# W032X.net
KiCad netlist of a schematic drawn in EAGLE
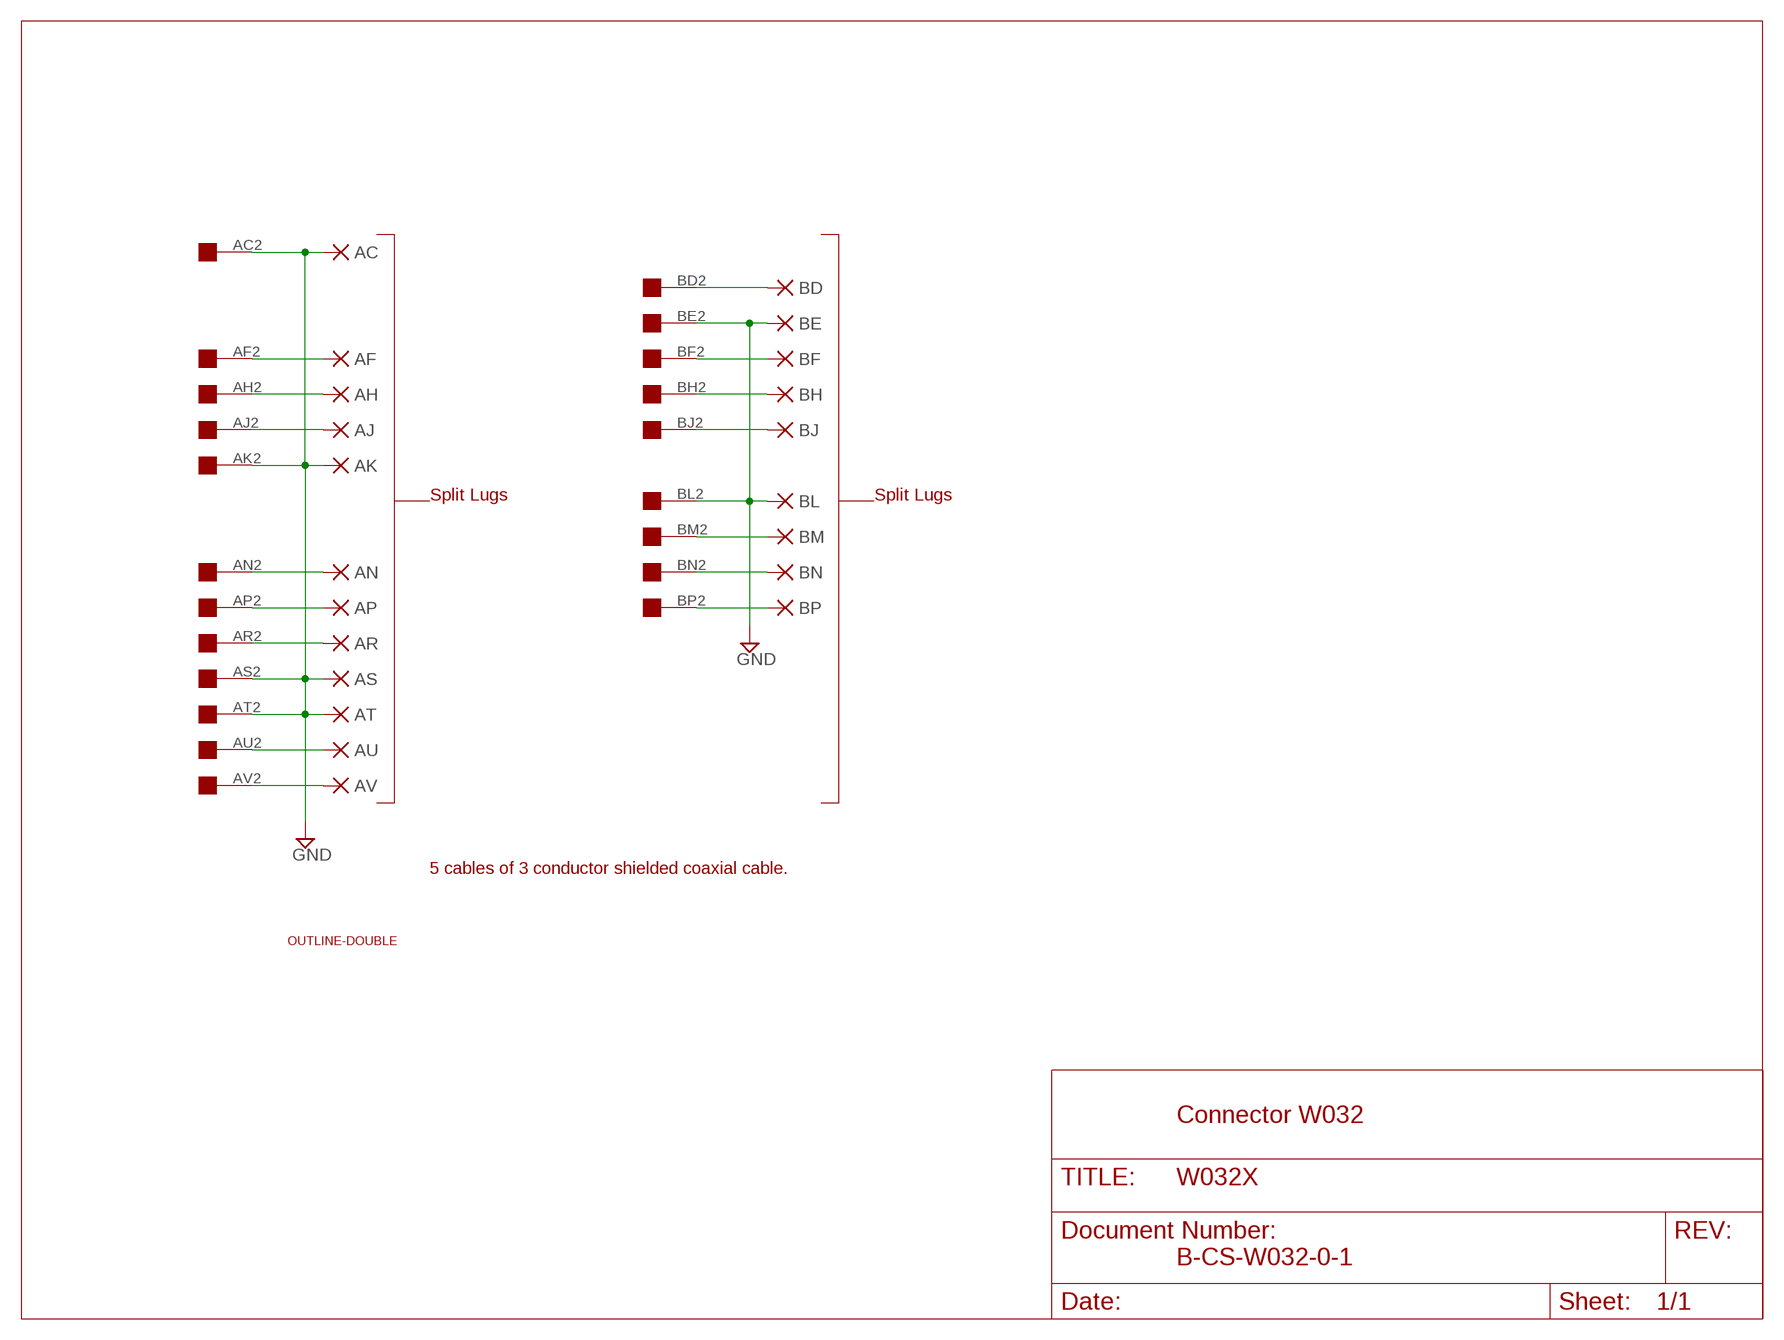
[diagram p0: schematic, sheet 1]

(export (version "E")
  (design (tool "Eeschema 10.0.6"))
  (components
    (comp (ref "AC")
      (value "PAD-0465")
      (footprint "eagle-import:0465")
      (libsource (lib "eagle-import") (part "PAD-0465"))
    )
    (comp (ref "AF")
      (value "PAD-0465")
      (footprint "eagle-import:0465")
      (libsource (lib "eagle-import") (part "PAD-0465"))
    )
    (comp (ref "AH")
      (value "PAD-0465")
      (footprint "eagle-import:0465")
      (libsource (lib "eagle-import") (part "PAD-0465"))
    )
    (comp (ref "AJ")
      (value "PAD-0465")
      (footprint "eagle-import:0465")
      (libsource (lib "eagle-import") (part "PAD-0465"))
    )
    (comp (ref "AK")
      (value "PAD-0465")
      (footprint "eagle-import:0465")
      (libsource (lib "eagle-import") (part "PAD-0465"))
    )
    (comp (ref "AN")
      (value "PAD-0465")
      (footprint "eagle-import:0465")
      (libsource (lib "eagle-import") (part "PAD-0465"))
    )
    (comp (ref "AP")
      (value "PAD-0465")
      (footprint "eagle-import:0465")
      (libsource (lib "eagle-import") (part "PAD-0465"))
    )
    (comp (ref "AR")
      (value "PAD-0465")
      (footprint "eagle-import:0465")
      (libsource (lib "eagle-import") (part "PAD-0465"))
    )
    (comp (ref "AS")
      (value "PAD-0465")
      (footprint "eagle-import:0465")
      (libsource (lib "eagle-import") (part "PAD-0465"))
    )
    (comp (ref "AT")
      (value "PAD-0465")
      (footprint "eagle-import:0465")
      (libsource (lib "eagle-import") (part "PAD-0465"))
    )
    (comp (ref "AU")
      (value "PAD-0465")
      (footprint "eagle-import:0465")
      (libsource (lib "eagle-import") (part "PAD-0465"))
    )
    (comp (ref "AV")
      (value "PAD-0465")
      (footprint "eagle-import:0465")
      (libsource (lib "eagle-import") (part "PAD-0465"))
    )
    (comp (ref "BD")
      (value "PAD-0465")
      (footprint "eagle-import:0465")
      (libsource (lib "eagle-import") (part "PAD-0465"))
    )
    (comp (ref "BE")
      (value "PAD-0465")
      (footprint "eagle-import:0465")
      (libsource (lib "eagle-import") (part "PAD-0465"))
    )
    (comp (ref "BF")
      (value "PAD-0465")
      (footprint "eagle-import:0465")
      (libsource (lib "eagle-import") (part "PAD-0465"))
    )
    (comp (ref "BH")
      (value "PAD-0465")
      (footprint "eagle-import:0465")
      (libsource (lib "eagle-import") (part "PAD-0465"))
    )
    (comp (ref "BJ")
      (value "PAD-0465")
      (footprint "eagle-import:0465")
      (libsource (lib "eagle-import") (part "PAD-0465"))
    )
    (comp (ref "BL")
      (value "PAD-0465")
      (footprint "eagle-import:0465")
      (libsource (lib "eagle-import") (part "PAD-0465"))
    )
    (comp (ref "BM")
      (value "PAD-0465")
      (footprint "eagle-import:0465")
      (libsource (lib "eagle-import") (part "PAD-0465"))
    )
    (comp (ref "BN")
      (value "PAD-0465")
      (footprint "eagle-import:0465")
      (libsource (lib "eagle-import") (part "PAD-0465"))
    )
    (comp (ref "BP")
      (value "PAD-0465")
      (footprint "eagle-import:0465")
      (libsource (lib "eagle-import") (part "PAD-0465"))
    )
    (comp (ref "U$1")
      (value "OUTLINE-DOUBLE")
      (footprint "eagle-import:DOUBLE")
      (libsource (lib "eagle-import") (part "OUTLINE-DOUBLE"))
    )
    (comp (ref "U$3")
      (value "DOUBLE")
      (footprint "eagle-import:EDGE-CON4")
      (libsource (lib "eagle-import") (part "DOUBLE"))
    )
  )
  (nets
    (net (code "1") (name "GND") (class "Default")
      (node (ref "AC") (pin "P$1") (pinfunction "P_P$1") (pintype "passive"))
      (node (ref "AK") (pin "P$1") (pinfunction "P_P$1") (pintype "passive"))
      (node (ref "AS") (pin "P$1") (pinfunction "P_P$1") (pintype "passive"))
      (node (ref "AT") (pin "P$1") (pinfunction "P_P$1") (pintype "passive"))
      (node (ref "BE") (pin "P$1") (pinfunction "P_P$1") (pintype "passive"))
      (node (ref "BL") (pin "P$1") (pinfunction "P_P$1") (pintype "passive"))
      (node (ref "U$3") (pin "AC2") (pinfunction "1_AC2") (pintype "bidirectional"))
      (node (ref "U$3") (pin "AK2") (pinfunction "1_AK2") (pintype "bidirectional"))
      (node (ref "U$3") (pin "AS2") (pinfunction "1_AS2") (pintype "bidirectional"))
      (node (ref "U$3") (pin "AT2") (pinfunction "1_AT2") (pintype "bidirectional"))
      (node (ref "U$3") (pin "BE2") (pinfunction "1_BE2") (pintype "bidirectional"))
      (node (ref "U$3") (pin "BL2") (pinfunction "1_BL2") (pintype "bidirectional"))
    )
    (net (code "2") (name "Net-(AF-P)") (class "Default")
      (node (ref "AF") (pin "P$1") (pinfunction "P_P$1") (pintype "passive"))
      (node (ref "U$3") (pin "AF2") (pinfunction "1_AF2") (pintype "bidirectional"))
    )
    (net (code "3") (name "Net-(AH-P)") (class "Default")
      (node (ref "AH") (pin "P$1") (pinfunction "P_P$1") (pintype "passive"))
      (node (ref "U$3") (pin "AH2") (pinfunction "1_AH2") (pintype "bidirectional"))
    )
    (net (code "4") (name "Net-(AJ-P)") (class "Default")
      (node (ref "AJ") (pin "P$1") (pinfunction "P_P$1") (pintype "passive"))
      (node (ref "U$3") (pin "AJ2") (pinfunction "1_AJ2") (pintype "bidirectional"))
    )
    (net (code "5") (name "Net-(AN-P)") (class "Default")
      (node (ref "AN") (pin "P$1") (pinfunction "P_P$1") (pintype "passive"))
      (node (ref "U$3") (pin "AN2") (pinfunction "1_AN2") (pintype "bidirectional"))
    )
    (net (code "6") (name "Net-(AP-P)") (class "Default")
      (node (ref "AP") (pin "P$1") (pinfunction "P_P$1") (pintype "passive"))
      (node (ref "U$3") (pin "AP2") (pinfunction "1_AP2") (pintype "bidirectional"))
    )
    (net (code "7") (name "Net-(AR-P)") (class "Default")
      (node (ref "AR") (pin "P$1") (pinfunction "P_P$1") (pintype "passive"))
      (node (ref "U$3") (pin "AR2") (pinfunction "1_AR2") (pintype "bidirectional"))
    )
    (net (code "8") (name "Net-(AU-P)") (class "Default")
      (node (ref "AU") (pin "P$1") (pinfunction "P_P$1") (pintype "passive"))
      (node (ref "U$3") (pin "AU2") (pinfunction "1_AU2") (pintype "bidirectional"))
    )
    (net (code "9") (name "Net-(AV-P)") (class "Default")
      (node (ref "AV") (pin "P$1") (pinfunction "P_P$1") (pintype "passive"))
      (node (ref "U$3") (pin "AV2") (pinfunction "1_AV2") (pintype "bidirectional"))
    )
    (net (code "10") (name "Net-(BD-P)") (class "Default")
      (node (ref "BD") (pin "P$1") (pinfunction "P_P$1") (pintype "passive"))
      (node (ref "U$3") (pin "BD2") (pinfunction "1_BD2") (pintype "bidirectional"))
    )
    (net (code "11") (name "Net-(BF-P)") (class "Default")
      (node (ref "BF") (pin "P$1") (pinfunction "P_P$1") (pintype "passive"))
      (node (ref "U$3") (pin "BF2") (pinfunction "1_BF2") (pintype "bidirectional"))
    )
    (net (code "12") (name "Net-(BH-P)") (class "Default")
      (node (ref "BH") (pin "P$1") (pinfunction "P_P$1") (pintype "passive"))
      (node (ref "U$3") (pin "BH2") (pinfunction "1_BH2") (pintype "bidirectional"))
    )
    (net (code "13") (name "Net-(BJ-P)") (class "Default")
      (node (ref "BJ") (pin "P$1") (pinfunction "P_P$1") (pintype "passive"))
      (node (ref "U$3") (pin "BJ2") (pinfunction "1_BJ2") (pintype "bidirectional"))
    )
    (net (code "14") (name "Net-(BM-P)") (class "Default")
      (node (ref "BM") (pin "P$1") (pinfunction "P_P$1") (pintype "passive"))
      (node (ref "U$3") (pin "BM2") (pinfunction "1_BM2") (pintype "bidirectional"))
    )
    (net (code "15") (name "Net-(BN-P)") (class "Default")
      (node (ref "BN") (pin "P$1") (pinfunction "P_P$1") (pintype "passive"))
      (node (ref "U$3") (pin "BN2") (pinfunction "1_BN2") (pintype "bidirectional"))
    )
    (net (code "16") (name "Net-(BP-P)") (class "Default")
      (node (ref "BP") (pin "P$1") (pinfunction "P_P$1") (pintype "passive"))
      (node (ref "U$3") (pin "BP2") (pinfunction "1_BP2") (pintype "bidirectional"))
    )
  )
)
